# LED.net
KiCad netlist of a schematic drawn in Altium Designer
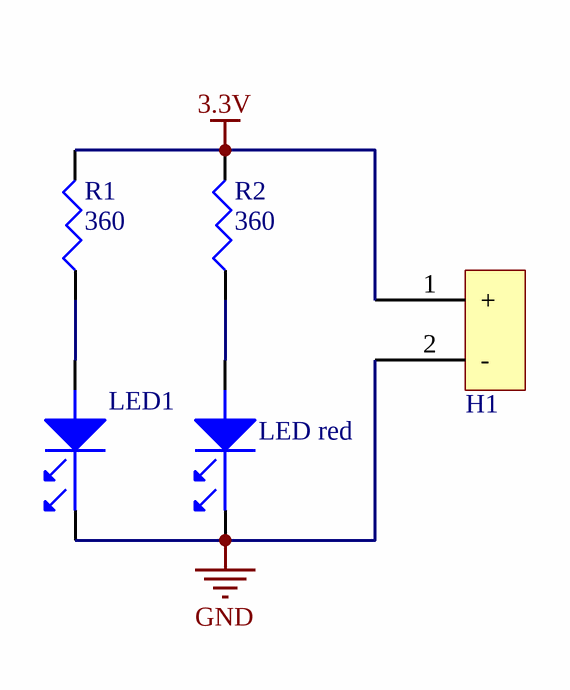
[diagram p0: LED.SchDoc]

(export (version "E")
  (design (tool "Eeschema 10.0.6"))
  (components
    (comp (ref "H1")
      (value "Connector Header Through Hole 2 position")
      (footprint "Header 1x2")
      (libsource (lib "LED1") (part "Header  Hole 2"))
    )
    (comp (ref "LED1")
      (value "LED red")
      (footprint "LED-red")
      (description "Red 617nm LED Indication - Discrete 1.9V Radial")
      (libsource (lib "LED1") (part "LED red"))
    )
    (comp (ref "LED2")
      (value "LED red")
      (footprint "LED-red")
      (description "Red 617nm LED Indication - Discrete 1.9V Radial")
      (libsource (lib "LED1") (part "LED red"))
    )
    (comp (ref "R1")
      (value "360")
      (footprint "R0805 - duplicate")
      (description "AC0805FR-07360RL")
      (libsource (lib "LED1") (part "Resistor"))
    )
    (comp (ref "R2")
      (value "360")
      (footprint "R0805 - duplicate")
      (description "AC0805FR-07360RL")
      (libsource (lib "LED1") (part "Resistor"))
    )
  )
  (nets
    (net (code "1") (name "3.3V") (class "Default")
      (node (ref "H1") (pin "1") (pinfunction "+_1") (pintype "passive"))
      (node (ref "R1") (pin "2") (pinfunction "2_2") (pintype "passive"))
      (node (ref "R2") (pin "2") (pinfunction "2_2") (pintype "passive"))
    )
    (net (code "2") (name "GND") (class "Default")
      (node (ref "H1") (pin "2") (pinfunction "-_2") (pintype "passive"))
      (node (ref "LED1") (pin "1") (pintype "passive"))
      (node (ref "LED2") (pin "1") (pintype "passive"))
    )
    (net (code "3") (name "Net-(LED1-Pad2)") (class "Default")
      (node (ref "LED1") (pin "2") (pintype "passive"))
      (node (ref "R1") (pin "1") (pinfunction "1_1") (pintype "passive"))
    )
    (net (code "4") (name "Net-(LED2-Pad2)") (class "Default")
      (node (ref "LED2") (pin "2") (pintype "passive"))
      (node (ref "R2") (pin "1") (pinfunction "1_1") (pintype "passive"))
    )
  )
)
